# pingLED.net
KiCad netlist of a schematic drawn in EAGLE
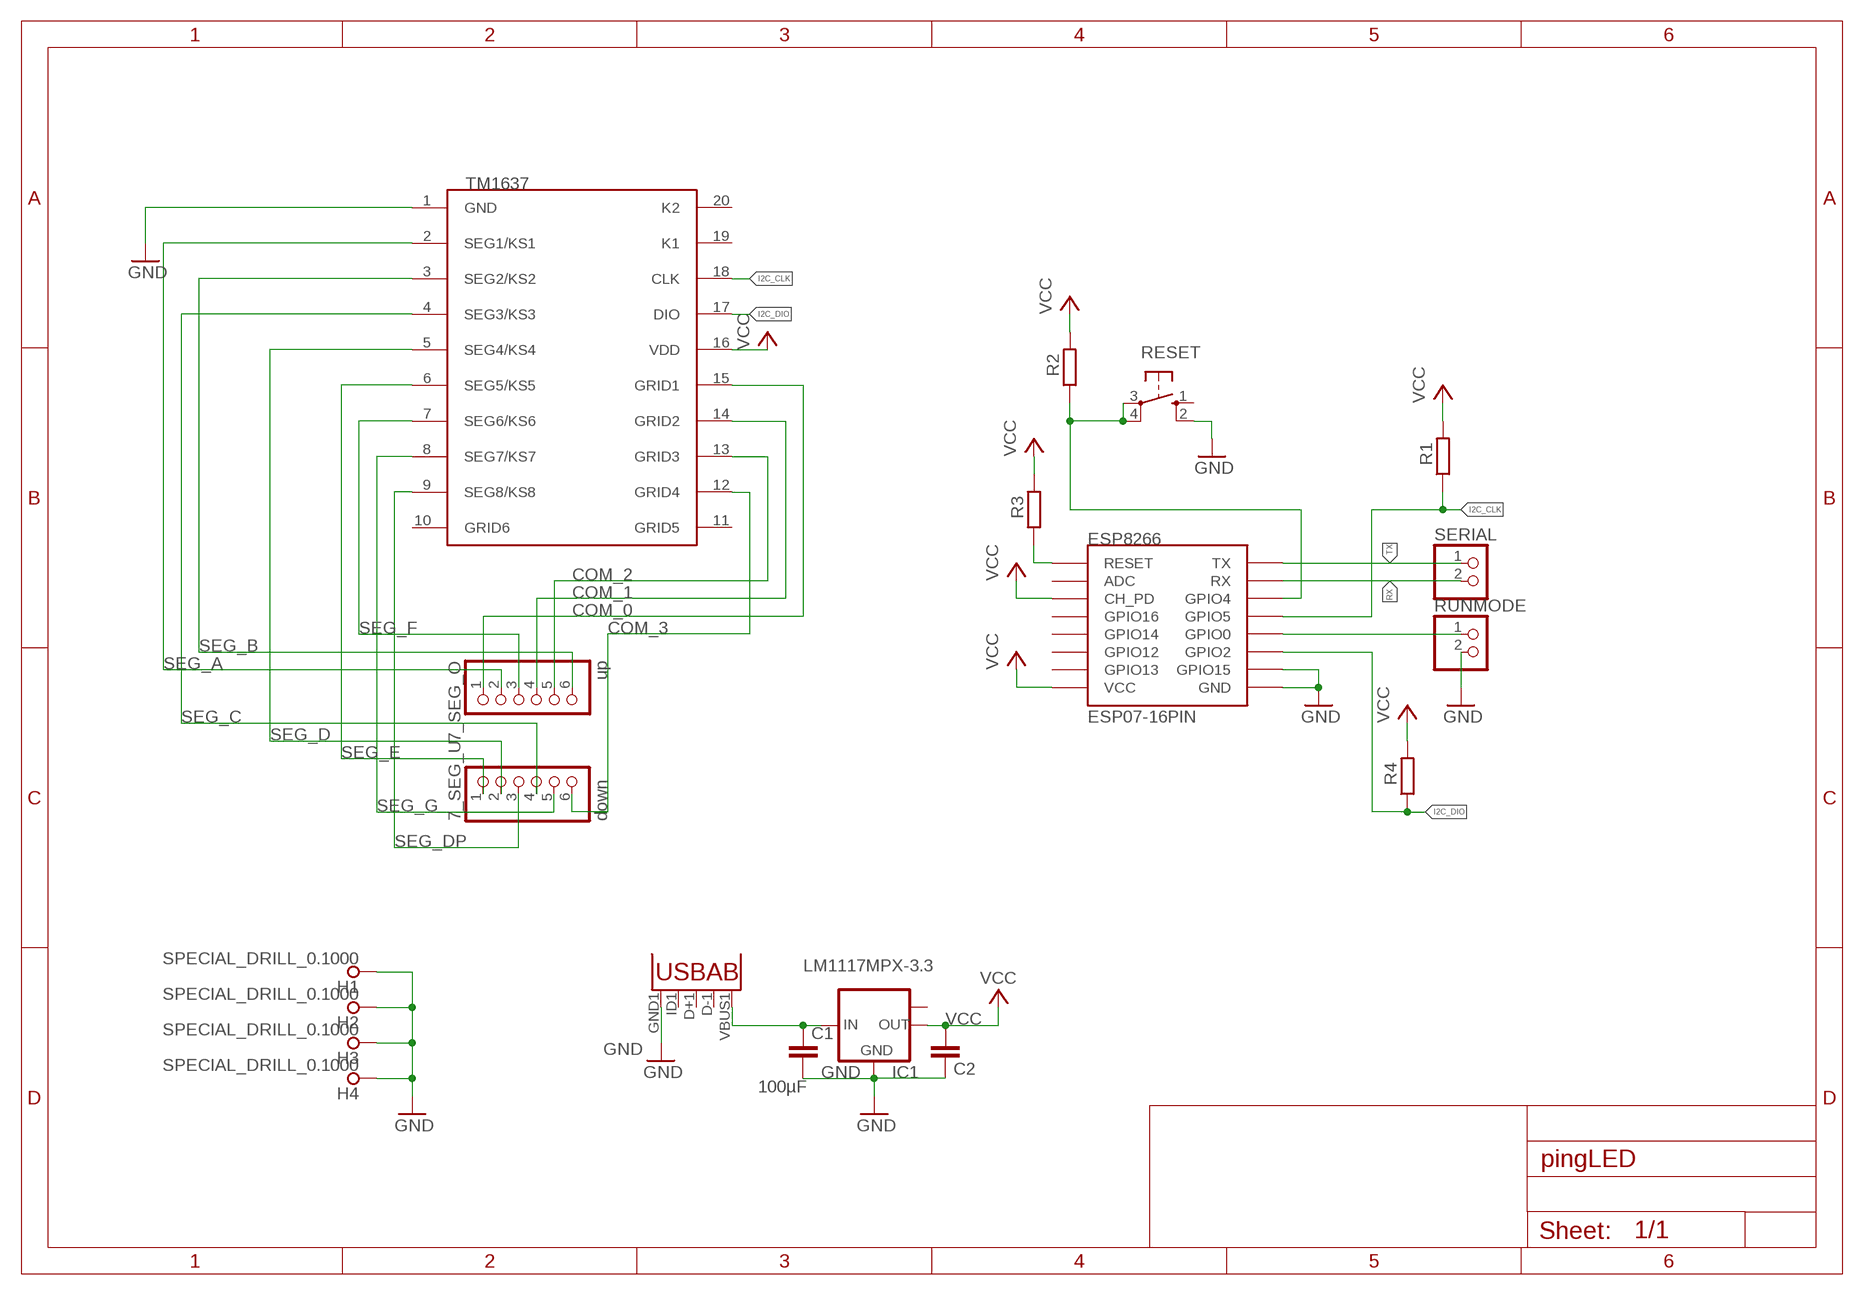
[diagram p0: schematic, sheet 1]

(export (version "E")
  (design (tool "Eeschema 10.0.6"))
  (components
    (comp (ref "7SEG_DRIVER")
      (value "TM1637SOP20")
      (footprint "eagle-import:SOIC127P1045X255-20")
      (libsource (lib "eagle-import") (part "TM1637SOP20"))
    )
    (comp (ref "7_SEG_O")
      (value "up")
      (footprint "eagle-import:1X06")
      (libsource (lib "eagle-import") (part "PINHD-1X6"))
    )
    (comp (ref "7_SEG_U")
      (value "down")
      (footprint "eagle-import:1X06")
      (libsource (lib "eagle-import") (part "PINHD-1X6"))
    )
    (comp (ref "C1")
      (value "100µF")
      (footprint "eagle-import:C0603")
      (libsource (lib "eagle-import") (part "C-EUC0603"))
    )
    (comp (ref "C2")
      (value "C-EUC0603")
      (footprint "eagle-import:C0603")
      (libsource (lib "eagle-import") (part "C-EUC0603"))
    )
    (comp (ref "ESP8266")
      (value "ESP07-16PIN")
      (footprint "eagle-import:ESP07-16PIN")
      (libsource (lib "eagle-import") (part "ESP07-16PIN"))
    )
    (comp (ref "H1")
      (value "SPECIAL_DRILL_0.1000")
      (footprint "eagle-import:PAD_0.1000")
      (libsource (lib "eagle-import") (part "SPECIAL_DRILL_0.1000"))
    )
    (comp (ref "H2")
      (value "SPECIAL_DRILL_0.1000")
      (footprint "eagle-import:PAD_0.1000")
      (libsource (lib "eagle-import") (part "SPECIAL_DRILL_0.1000"))
    )
    (comp (ref "H3")
      (value "SPECIAL_DRILL_0.1000")
      (footprint "eagle-import:PAD_0.1000")
      (libsource (lib "eagle-import") (part "SPECIAL_DRILL_0.1000"))
    )
    (comp (ref "H4")
      (value "SPECIAL_DRILL_0.1000")
      (footprint "eagle-import:PAD_0.1000")
      (libsource (lib "eagle-import") (part "SPECIAL_DRILL_0.1000"))
    )
    (comp (ref "IC1")
      (value "LM1117MPX-3.3")
      (footprint "eagle-import:SOT223")
      (libsource (lib "eagle-import") (part "LM1117MPX-3.3"))
    )
    (comp (ref "R1")
      (value "R-EU_R0603")
      (footprint "eagle-import:R0603")
      (libsource (lib "eagle-import") (part "R-EU_R0603"))
    )
    (comp (ref "R2")
      (value "R-EU_R0603")
      (footprint "eagle-import:R0603")
      (libsource (lib "eagle-import") (part "R-EU_R0603"))
    )
    (comp (ref "R3")
      (value "R-EU_R0603")
      (footprint "eagle-import:R0603")
      (libsource (lib "eagle-import") (part "R-EU_R0603"))
    )
    (comp (ref "R4")
      (value "R-EU_R0603")
      (footprint "eagle-import:R0603")
      (libsource (lib "eagle-import") (part "R-EU_R0603"))
    )
    (comp (ref "RESET")
      (value "10-XX")
      (footprint "eagle-import:B3F-10XX")
      (fields (field (name "MPN") "B3F-1000"))
      (libsource (lib "eagle-import") (part "10-XX"))
    )
    (comp (ref "RUNMODE")
      (value "PINHD-1X2")
      (footprint "eagle-import:1X02")
      (libsource (lib "eagle-import") (part "PINHD-1X2"))
    )
    (comp (ref "SERIAL")
      (value "PINHD-1X2")
      (footprint "eagle-import:1X02")
      (libsource (lib "eagle-import") (part "PINHD-1X2"))
    )
    (comp (ref "U1")
      (value "V_IN")
      (footprint "eagle-import:USB-MICRO-SMD")
      (libsource (lib "eagle-import") (part "USB{dblquote}{dblquote}"))
    )
  )
  (nets
    (net (code "1") (name "/COM_0") (class "Default")
      (node (ref "7SEG_DRIVER") (pin "15") (pinfunction "GRID1_15") (pintype "bidirectional"))
      (node (ref "7_SEG_O") (pin "1") (pinfunction "1_1") (pintype "passive"))
    )
    (net (code "2") (name "/COM_1") (class "Default")
      (node (ref "7SEG_DRIVER") (pin "14") (pinfunction "GRID2_14") (pintype "bidirectional"))
      (node (ref "7_SEG_O") (pin "4") (pinfunction "4_4") (pintype "passive"))
    )
    (net (code "3") (name "/COM_2") (class "Default")
      (node (ref "7SEG_DRIVER") (pin "13") (pinfunction "GRID3_13") (pintype "bidirectional"))
      (node (ref "7_SEG_O") (pin "5") (pinfunction "5_5") (pintype "passive"))
    )
    (net (code "4") (name "/COM_3") (class "Default")
      (node (ref "7SEG_DRIVER") (pin "12") (pinfunction "GRID4_12") (pintype "bidirectional"))
      (node (ref "7_SEG_U") (pin "6") (pinfunction "6_6") (pintype "passive"))
    )
    (net (code "5") (name "/SEG_A") (class "Default")
      (node (ref "7SEG_DRIVER") (pin "2") (pinfunction "SEG1/KS1_2") (pintype "bidirectional"))
      (node (ref "7_SEG_O") (pin "2") (pinfunction "2_2") (pintype "passive"))
    )
    (net (code "6") (name "/SEG_B") (class "Default")
      (node (ref "7SEG_DRIVER") (pin "3") (pinfunction "SEG2/KS2_3") (pintype "bidirectional"))
      (node (ref "7_SEG_O") (pin "6") (pinfunction "6_6") (pintype "passive"))
    )
    (net (code "7") (name "/SEG_C") (class "Default")
      (node (ref "7SEG_DRIVER") (pin "4") (pinfunction "SEG3/KS3_4") (pintype "bidirectional"))
      (node (ref "7_SEG_U") (pin "4") (pinfunction "4_4") (pintype "passive"))
    )
    (net (code "8") (name "/SEG_D") (class "Default")
      (node (ref "7SEG_DRIVER") (pin "5") (pinfunction "SEG4/KS4_5") (pintype "bidirectional"))
      (node (ref "7_SEG_U") (pin "2") (pinfunction "2_2") (pintype "passive"))
    )
    (net (code "9") (name "/SEG_DP") (class "Default")
      (node (ref "7SEG_DRIVER") (pin "9") (pinfunction "SEG8/KS8_9") (pintype "bidirectional"))
      (node (ref "7_SEG_U") (pin "3") (pinfunction "3_3") (pintype "passive"))
    )
    (net (code "10") (name "/SEG_E") (class "Default")
      (node (ref "7SEG_DRIVER") (pin "6") (pinfunction "SEG5/KS5_6") (pintype "bidirectional"))
      (node (ref "7_SEG_U") (pin "1") (pinfunction "1_1") (pintype "passive"))
    )
    (net (code "11") (name "/SEG_F") (class "Default")
      (node (ref "7SEG_DRIVER") (pin "7") (pinfunction "SEG6/KS6_7") (pintype "bidirectional"))
      (node (ref "7_SEG_O") (pin "3") (pinfunction "3_3") (pintype "passive"))
    )
    (net (code "12") (name "/SEG_G") (class "Default")
      (node (ref "7SEG_DRIVER") (pin "8") (pinfunction "SEG7/KS7_8") (pintype "bidirectional"))
      (node (ref "7_SEG_U") (pin "5") (pinfunction "5_5") (pintype "passive"))
    )
    (net (code "13") (name "GND") (class "Default")
      (node (ref "7SEG_DRIVER") (pin "1") (pinfunction "GND_1") (pintype "bidirectional"))
      (node (ref "C1") (pin "2") (pinfunction "2_2") (pintype "passive"))
      (node (ref "C2") (pin "2") (pinfunction "2_2") (pintype "passive"))
      (node (ref "ESP8266") (pin "GND") (pinfunction "GND_GND") (pintype "bidirectional"))
      (node (ref "ESP8266") (pin "GPIO15") (pinfunction "GPIO15_GPIO15") (pintype "bidirectional"))
      (node (ref "H1") (pin "1") (pinfunction "1_1") (pintype "passive"))
      (node (ref "H2") (pin "1") (pinfunction "1_1") (pintype "passive"))
      (node (ref "H3") (pin "1") (pinfunction "1_1") (pintype "passive"))
      (node (ref "H4") (pin "1") (pinfunction "1_1") (pintype "passive"))
      (node (ref "IC1") (pin "1") (pinfunction "GND_1") (pintype "input"))
      (node (ref "RESET") (pin "2") (pinfunction "S1_2") (pintype "passive"))
      (node (ref "RUNMODE") (pin "2") (pinfunction "2_2") (pintype "passive"))
      (node (ref "U1") (pin "GND1") (pinfunction "GND_GND1") (pintype "bidirectional"))
    )
    (net (code "14") (name "I2C_CLK") (class "Default")
      (node (ref "7SEG_DRIVER") (pin "18") (pinfunction "CLK_18") (pintype "bidirectional"))
      (node (ref "ESP8266") (pin "GPIO5") (pinfunction "GPIO5_GPIO5") (pintype "bidirectional"))
      (node (ref "R1") (pin "1") (pinfunction "1_1") (pintype "passive"))
    )
    (net (code "15") (name "I2C_DIO") (class "Default")
      (node (ref "7SEG_DRIVER") (pin "17") (pinfunction "DIO_17") (pintype "bidirectional"))
      (node (ref "ESP8266") (pin "GPIO2") (pinfunction "GPIO2_GPIO2") (pintype "bidirectional"))
      (node (ref "R4") (pin "1") (pinfunction "1_1") (pintype "passive"))
    )
    (net (code "16") (name "Net-(ESP8266-PadGPIO0)") (class "Default")
      (node (ref "ESP8266") (pin "GPIO0") (pinfunction "GPIO0_GPIO0") (pintype "bidirectional"))
      (node (ref "RUNMODE") (pin "1") (pinfunction "1_1") (pintype "passive"))
    )
    (net (code "17") (name "Net-(ESP8266-RESET)") (class "Default")
      (node (ref "ESP8266") (pin "REST") (pinfunction "RESET_REST") (pintype "bidirectional"))
      (node (ref "R3") (pin "1") (pinfunction "1_1") (pintype "passive"))
    )
    (net (code "18") (name "Net-(IC1-IN)") (class "Default")
      (node (ref "C1") (pin "1") (pinfunction "1_1") (pintype "passive"))
      (node (ref "IC1") (pin "3") (pinfunction "IN_3") (pintype "input"))
      (node (ref "U1") (pin "VBUS1") (pinfunction "VBUS_VBUS1") (pintype "bidirectional"))
    )
    (net (code "19") (name "Net-(RESET-P)") (class "Default")
      (node (ref "ESP8266") (pin "GPIO4") (pinfunction "GPIO4_GPIO4") (pintype "bidirectional"))
      (node (ref "R2") (pin "1") (pinfunction "1_1") (pintype "passive"))
      (node (ref "RESET") (pin "3") (pinfunction "P_3") (pintype "passive"))
      (node (ref "RESET") (pin "4") (pinfunction "P1_4") (pintype "passive"))
    )
    (net (code "20") (name "RX") (class "Default")
      (node (ref "ESP8266") (pin "RX") (pinfunction "RX_RX") (pintype "bidirectional"))
      (node (ref "SERIAL") (pin "2") (pinfunction "2_2") (pintype "passive"))
    )
    (net (code "21") (name "TX") (class "Default")
      (node (ref "ESP8266") (pin "TX") (pinfunction "TX_TX") (pintype "bidirectional"))
      (node (ref "SERIAL") (pin "1") (pinfunction "1_1") (pintype "passive"))
    )
    (net (code "22") (name "VCC") (class "Default")
      (node (ref "7SEG_DRIVER") (pin "16") (pinfunction "VDD_16") (pintype "bidirectional"))
      (node (ref "C2") (pin "1") (pinfunction "1_1") (pintype "passive"))
      (node (ref "ESP8266") (pin "CH_PD") (pinfunction "CH_PD_CH_PD") (pintype "bidirectional"))
      (node (ref "ESP8266") (pin "VCC") (pinfunction "VCC_VCC") (pintype "bidirectional"))
      (node (ref "IC1") (pin "2") (pinfunction "OUT_2") (pintype "passive"))
      (node (ref "R1") (pin "2") (pinfunction "2_2") (pintype "passive"))
      (node (ref "R2") (pin "2") (pinfunction "2_2") (pintype "passive"))
      (node (ref "R3") (pin "2") (pinfunction "2_2") (pintype "passive"))
      (node (ref "R4") (pin "2") (pinfunction "2_2") (pintype "passive"))
    )
    (net (code "23") (name "unconnected-(7SEG_DRIVER-GRID5-Pad11)") (class "Default")
      (node (ref "7SEG_DRIVER") (pin "11") (pinfunction "GRID5_11") (pintype "bidirectional"))
    )
    (net (code "24") (name "unconnected-(7SEG_DRIVER-GRID6-Pad10)") (class "Default")
      (node (ref "7SEG_DRIVER") (pin "10") (pinfunction "GRID6_10") (pintype "bidirectional"))
    )
    (net (code "25") (name "unconnected-(7SEG_DRIVER-K1-Pad19)") (class "Default")
      (node (ref "7SEG_DRIVER") (pin "19") (pinfunction "K1_19") (pintype "bidirectional"))
    )
    (net (code "26") (name "unconnected-(7SEG_DRIVER-K2-Pad20)") (class "Default")
      (node (ref "7SEG_DRIVER") (pin "20") (pinfunction "K2_20") (pintype "bidirectional"))
    )
    (net (code "27") (name "unconnected-(ESP8266-PadADC)") (class "Default")
      (node (ref "ESP8266") (pin "ADC") (pinfunction "ADC_ADC") (pintype "bidirectional"))
    )
    (net (code "28") (name "unconnected-(ESP8266-PadGPIO12)") (class "Default")
      (node (ref "ESP8266") (pin "GPIO12") (pinfunction "GPIO12_GPIO12") (pintype "bidirectional"))
    )
    (net (code "29") (name "unconnected-(ESP8266-PadGPIO13)") (class "Default")
      (node (ref "ESP8266") (pin "GPIO13") (pinfunction "GPIO13_GPIO13") (pintype "bidirectional"))
    )
    (net (code "30") (name "unconnected-(ESP8266-PadGPIO14)") (class "Default")
      (node (ref "ESP8266") (pin "GPIO14") (pinfunction "GPIO14_GPIO14") (pintype "bidirectional"))
    )
    (net (code "31") (name "unconnected-(ESP8266-PadGPIO16)") (class "Default")
      (node (ref "ESP8266") (pin "GPIO16") (pinfunction "GPIO16_GPIO16") (pintype "bidirectional"))
    )
    (net (code "32") (name "unconnected-(IC1-OUT1-PadTAB)") (class "Default")
      (node (ref "IC1") (pin "TAB") (pinfunction "OUT1_TAB") (pintype "passive"))
    )
    (net (code "33") (name "unconnected-(RESET-S-Pad1)") (class "Default")
      (node (ref "RESET") (pin "1") (pinfunction "S_1") (pintype "passive"))
    )
    (net (code "34") (name "unconnected-(U1-D+-PadD+1)") (class "Default")
      (node (ref "U1") (pin "D+1") (pinfunction "D+_D+1") (pintype "bidirectional"))
    )
    (net (code "35") (name "unconnected-(U1-D--PadD-1)") (class "Default")
      (node (ref "U1") (pin "D-1") (pinfunction "D-_D-1") (pintype "bidirectional"))
    )
    (net (code "36") (name "unconnected-(U1-USBID-PadID1)") (class "Default")
      (node (ref "U1") (pin "ID1") (pinfunction "USBID_ID1") (pintype "bidirectional"))
    )
  )
)
